# Atomic_V1_0_LDO.net
KiCad netlist of a schematic drawn in EAGLE
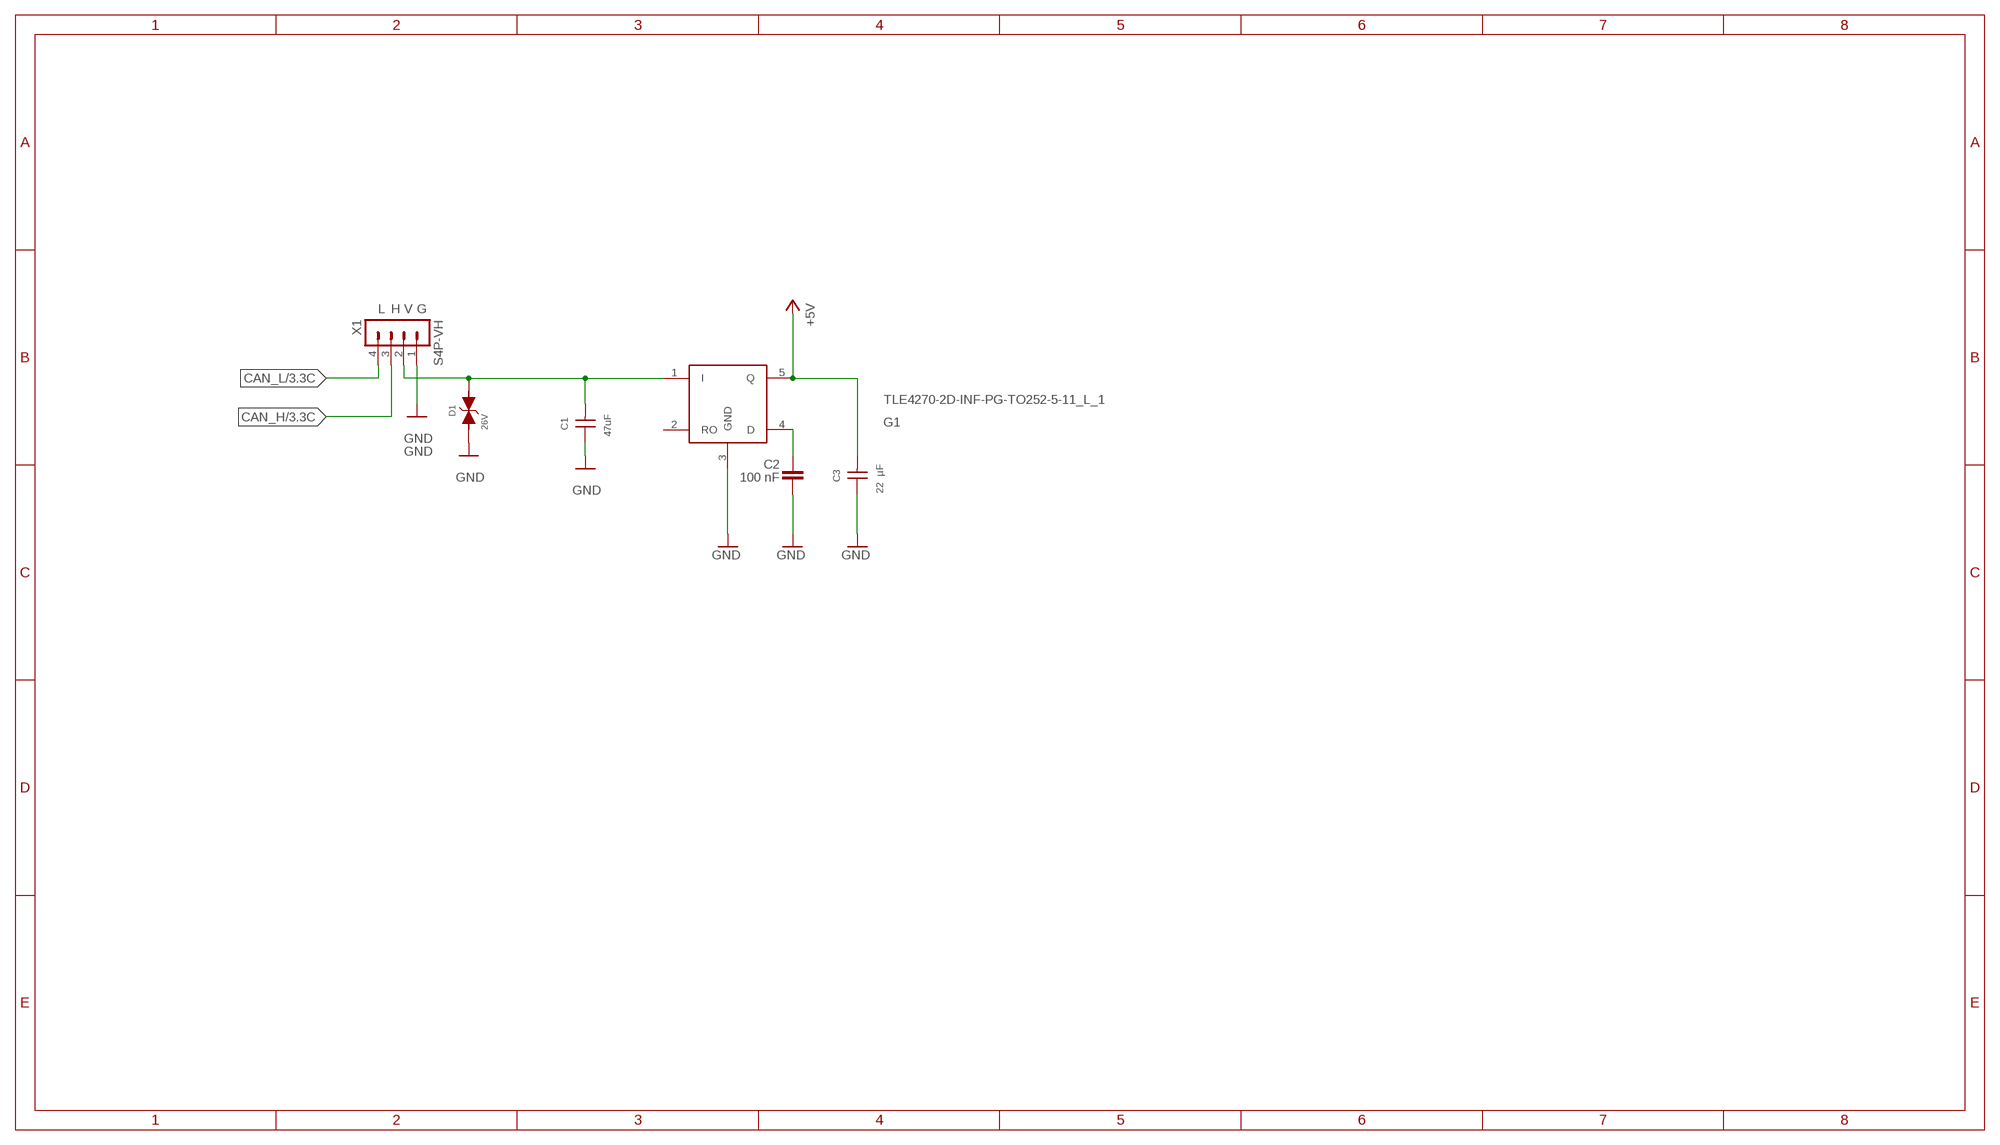
[diagram p0: schematic, sheet 1]
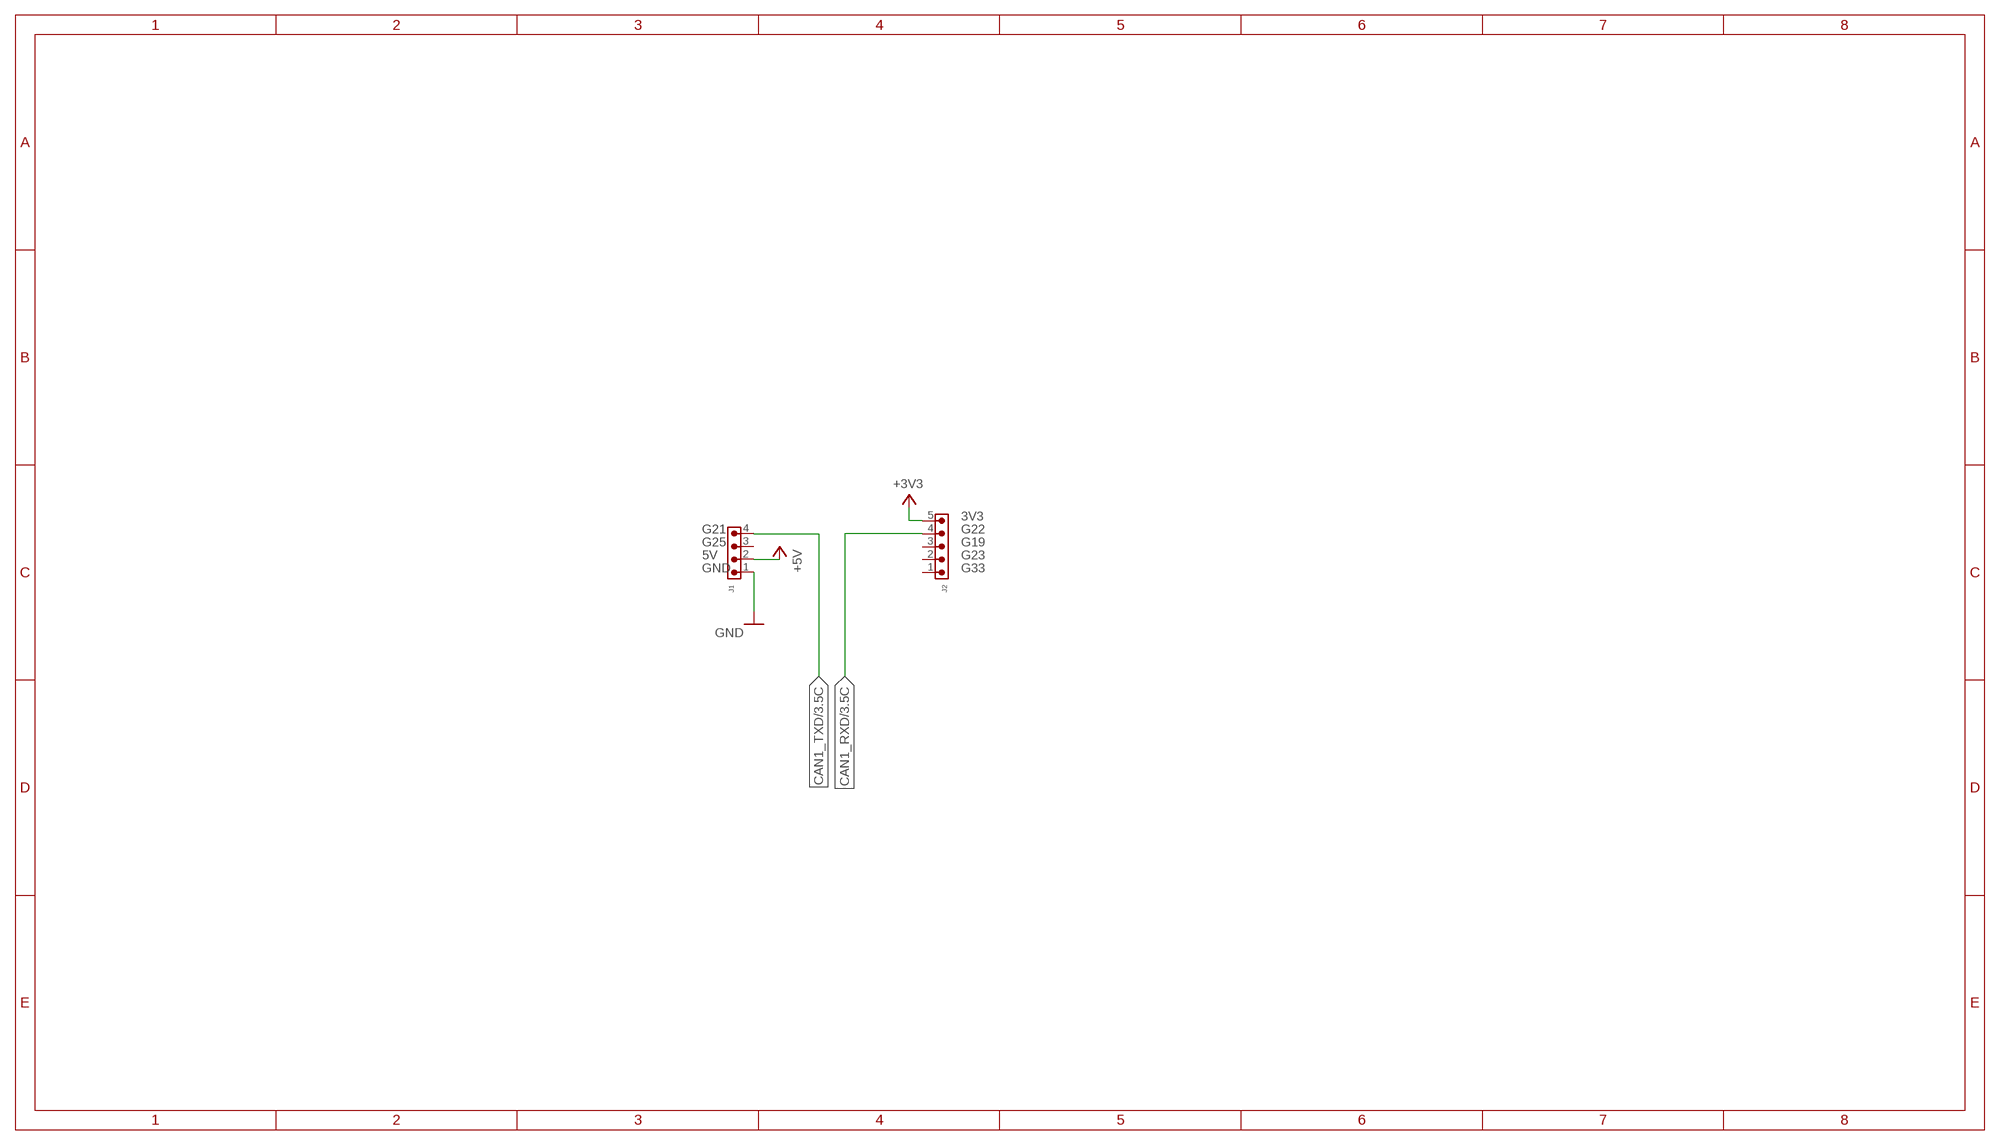
[diagram p1: schematic, sheet 2]
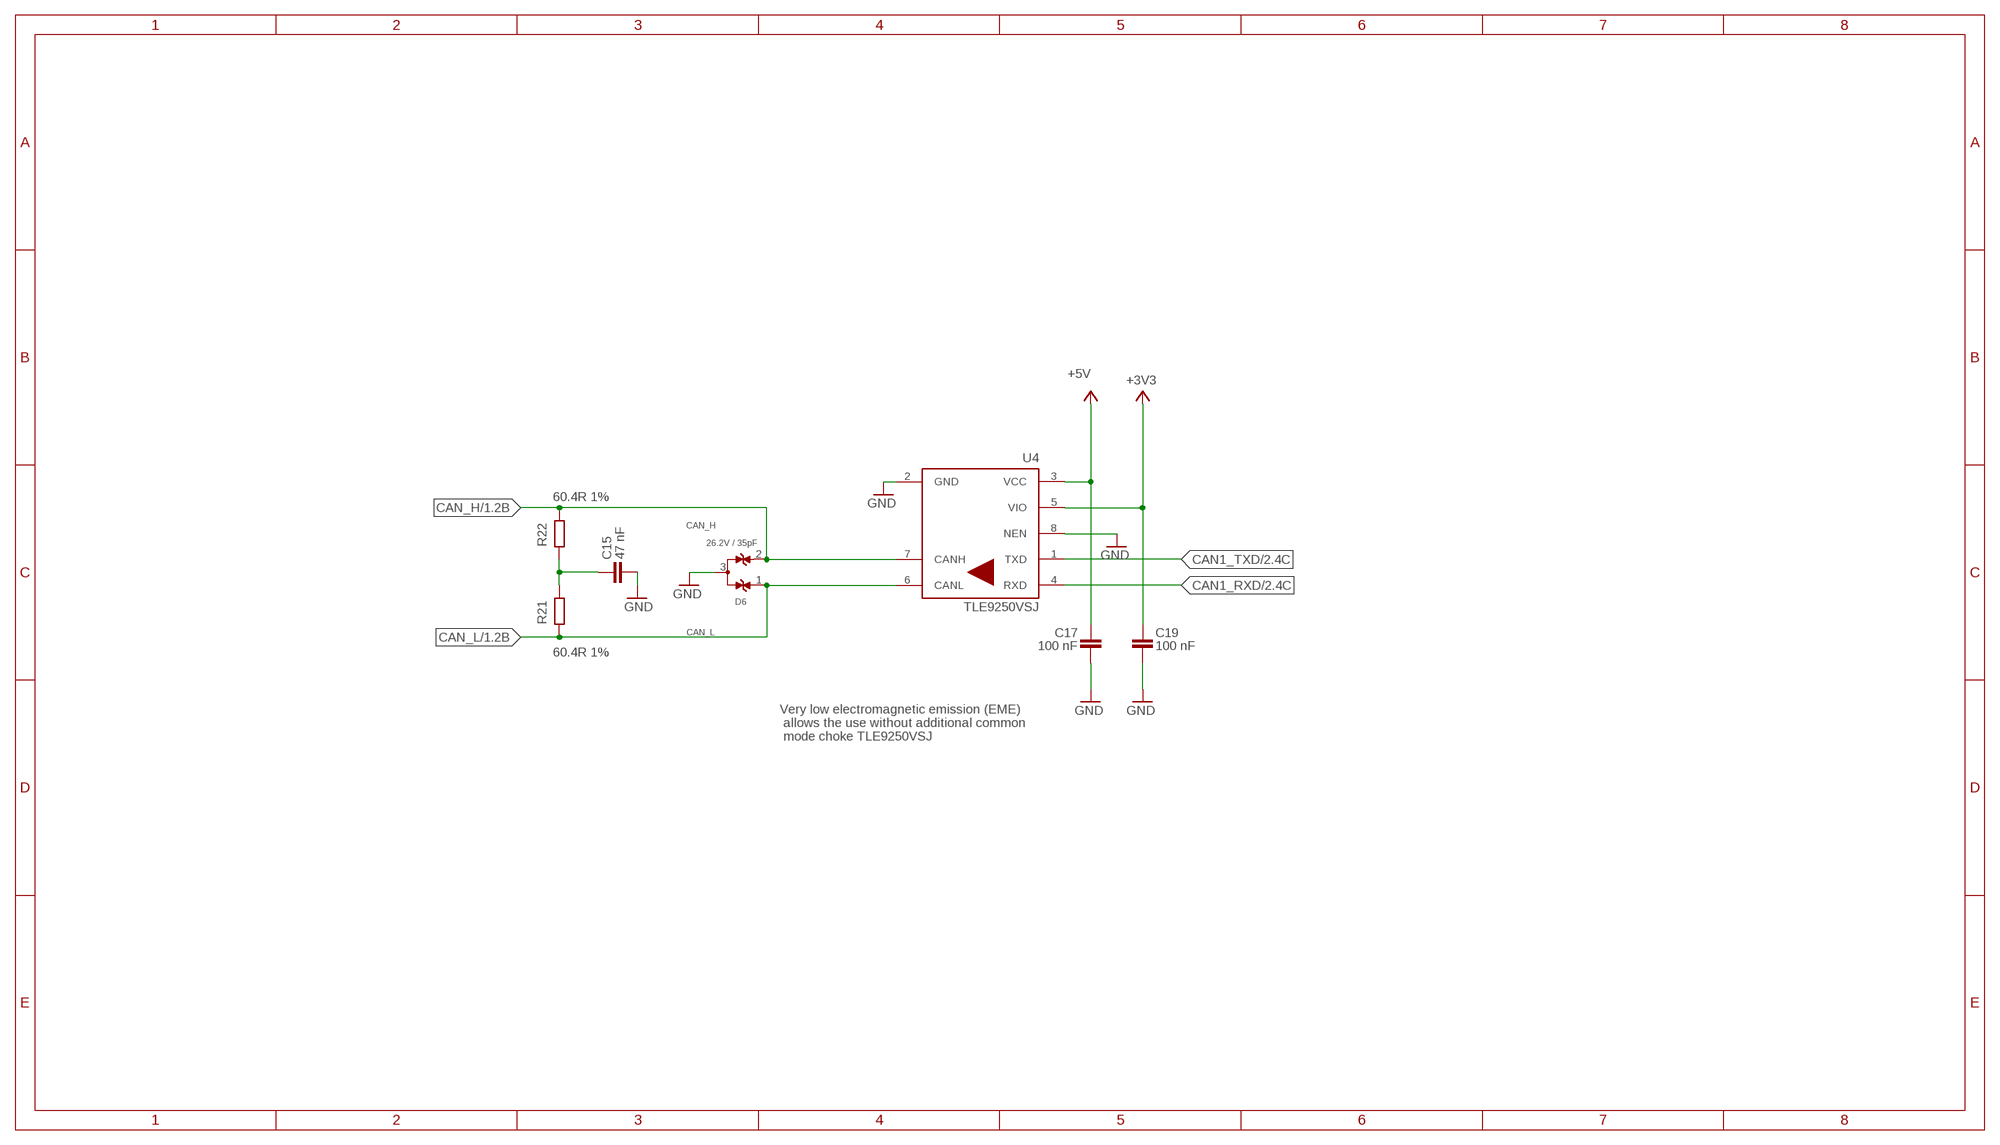
[diagram p2: schematic, sheet 3]

(export (version "E")
  (design (tool "Eeschema 10.0.6"))
  (components
    (comp (ref "C1")
      (value "47uF")
      (footprint "eagle-import:WCAP-CSGP_1210_H2.5")
      (libsource (lib "eagle-import") (part "WCAP-CSGP_1210_H2.5_25V(DC)_885012109014"))
    )
    (comp (ref "C2")
      (value "100 nF")
      (footprint "eagle-import:WCAP-CSGP_0402")
      (libsource (lib "eagle-import") (part "WCAP-CSGP_0402_16V(DC)_885012205037"))
    )
    (comp (ref "C3")
      (value "22 µF")
      (footprint "eagle-import:WCAP-CSGP_0805_H1.25_R")
      (libsource (lib "eagle-import") (part "WCAP-CSGP_0805_H1.25_10V(DC)_885012107011"))
    )
    (comp (ref "D1")
      (value "26V")
      (footprint "eagle-import:WE-TVSP_DO-214AC_BIDIRECTIONAL")
      (libsource (lib "eagle-import") (part "WE-TVSP_DO-214AC_400W_BI_824501261"))
    )
    (comp (ref "G1")
      (value "TLE4270-2D-INF-PG-TO252-5-11_L_1")
      (footprint "eagle-import:INF-PG-TO252-5-11_L_1PRIMARY")
      (libsource (lib "eagle-import") (part "TLE4270-2D-INF-PG-TO252-5-11_L_1"))
    )
    (comp (ref "X1")
      (value "S4P-VH")
      (footprint "eagle-import:S4P-VH")
      (libsource (lib "eagle-import") (part "S4P-VH"))
    )
    (comp (ref "J1")
      (value "6130XX11121_61300411121")
      (footprint "eagle-import:61300411121")
      (libsource (lib "eagle-import") (part "6130XX11121_61300411121"))
    )
    (comp (ref "J2")
      (value "6130XX11121_61300511121")
      (footprint "eagle-import:61300511121")
      (libsource (lib "eagle-import") (part "6130XX11121_61300511121"))
    )
    (comp (ref "C15")
      (value "47 nF")
      (footprint "eagle-import:WCAP-CSGP_0402")
      (libsource (lib "eagle-import") (part "WCAP-CSGP_0402_25V(DC)_885012205054"))
    )
    (comp (ref "C17")
      (value "100 nF")
      (footprint "eagle-import:WCAP-CSGP_0402")
      (libsource (lib "eagle-import") (part "WCAP-CSGP_0402_16V(DC)_885012205037"))
    )
    (comp (ref "C19")
      (value "100 nF")
      (footprint "eagle-import:WCAP-CSGP_0402")
      (libsource (lib "eagle-import") (part "WCAP-CSGP_0402_16V(DC)_885012205037"))
    )
    (comp (ref "D6")
      (value "26.2V / 35pF")
      (footprint "eagle-import:WE-TVS_SOT23-3L")
      (libsource (lib "eagle-import") (part "WE-TVS_SOT23-3L_824098024"))
    )
    (comp (ref "R21")
      (value "60.4R 1%")
      (footprint "eagle-import:WCAP-CSRF_0402")
      (fields (field (name "N") "SMD 0402 60.4ohms 1% AEC-Q200"))
      (libsource (lib "eagle-import") (part "R-0402_60.4OHMS_1%_AEC-Q200"))
    )
    (comp (ref "R22")
      (value "60.4R 1%")
      (footprint "eagle-import:WCAP-CSRF_0402")
      (fields (field (name "N") "SMD 0402 60.4ohms 1% AEC-Q200"))
      (libsource (lib "eagle-import") (part "R-0402_60.4OHMS_1%_AEC-Q200"))
    )
    (comp (ref "U4")
      (value "TLE9250VSJ")
      (footprint "eagle-import:SOIC127P602X173-8N-V")
      (libsource (lib "eagle-import") (part "TLE9250VSJ"))
    )
  )
  (nets
    (net (code "1") (name "+3V3") (class "Default")
      (node (ref "C19") (pin "1") (pinfunction "1_1") (pintype "passive"))
      (node (ref "J2") (pin "5") (pinfunction "5_5") (pintype "passive"))
      (node (ref "U4") (pin "5") (pinfunction "VIO_5") (pintype "input"))
    )
    (net (code "2") (name "+5V") (class "Default")
      (node (ref "C17") (pin "1") (pinfunction "1_1") (pintype "passive"))
      (node (ref "C3") (pin "2") (pinfunction "2_2") (pintype "passive"))
      (node (ref "G1") (pin "5") (pinfunction "Q_5") (pintype "power_in"))
      (node (ref "J1") (pin "2") (pinfunction "2_2") (pintype "passive"))
      (node (ref "U4") (pin "3") (pinfunction "VCC_3") (pintype "input"))
    )
    (net (code "3") (name "CAN1_RXD") (class "Default")
      (node (ref "J2") (pin "4") (pinfunction "4_4") (pintype "passive"))
      (node (ref "U4") (pin "4") (pinfunction "RXD_4") (pintype "output"))
    )
    (net (code "4") (name "CAN1_TXD") (class "Default")
      (node (ref "J1") (pin "4") (pinfunction "4_4") (pintype "passive"))
      (node (ref "U4") (pin "1") (pinfunction "TXD_1") (pintype "input"))
    )
    (net (code "5") (name "CAN_H") (class "Default")
      (node (ref "D6") (pin "2") (pinfunction "2_2") (pintype "passive"))
      (node (ref "R22") (pin "2") (pinfunction "2_2") (pintype "passive"))
      (node (ref "U4") (pin "7") (pinfunction "CANH_7") (pintype "bidirectional"))
      (node (ref "X1") (pin "3") (pinfunction "3_3") (pintype "passive"))
    )
    (net (code "6") (name "CAN_L") (class "Default")
      (node (ref "D6") (pin "1") (pinfunction "1_1") (pintype "passive"))
      (node (ref "R21") (pin "1") (pinfunction "1_1") (pintype "passive"))
      (node (ref "U4") (pin "6") (pinfunction "CANL_6") (pintype "bidirectional"))
      (node (ref "X1") (pin "4") (pinfunction "4_4") (pintype "passive"))
    )
    (net (code "7") (name "GND") (class "Default")
      (node (ref "C1") (pin "1") (pinfunction "1_1") (pintype "passive"))
      (node (ref "C15") (pin "2") (pinfunction "2_2") (pintype "passive"))
      (node (ref "C17") (pin "2") (pinfunction "2_2") (pintype "passive"))
      (node (ref "C19") (pin "2") (pinfunction "2_2") (pintype "passive"))
      (node (ref "C2") (pin "2") (pinfunction "2_2") (pintype "passive"))
      (node (ref "C3") (pin "1") (pinfunction "1_1") (pintype "passive"))
      (node (ref "D1") (pin "1") (pinfunction "1_1") (pintype "passive"))
      (node (ref "D6") (pin "3") (pinfunction "3_3") (pintype "passive"))
      (node (ref "G1") (pin "3") (pinfunction "GND_3") (pintype "power_in"))
      (node (ref "J1") (pin "1") (pinfunction "1_1") (pintype "passive"))
      (node (ref "U4") (pin "2") (pinfunction "GND_2") (pintype "power_in"))
      (node (ref "U4") (pin "8") (pinfunction "NEN_8") (pintype "input"))
      (node (ref "X1") (pin "1") (pinfunction "1_1") (pintype "passive"))
    )
    (net (code "8") (name "Net-(C15-Pad1)") (class "Default")
      (node (ref "C15") (pin "1") (pinfunction "1_1") (pintype "passive"))
      (node (ref "R21") (pin "2") (pinfunction "2_2") (pintype "passive"))
      (node (ref "R22") (pin "1") (pinfunction "1_1") (pintype "passive"))
    )
    (net (code "9") (name "Net-(G1-D)") (class "Default")
      (node (ref "C2") (pin "1") (pinfunction "1_1") (pintype "passive"))
      (node (ref "G1") (pin "4") (pinfunction "D_4") (pintype "bidirectional"))
    )
    (net (code "10") (name "Net-(G1-I)") (class "Default")
      (node (ref "C1") (pin "2") (pinfunction "2_2") (pintype "passive"))
      (node (ref "D1") (pin "2") (pinfunction "2_2") (pintype "passive"))
      (node (ref "G1") (pin "1") (pinfunction "I_1") (pintype "power_in"))
      (node (ref "X1") (pin "2") (pinfunction "2_2") (pintype "passive"))
    )
    (net (code "11") (name "unconnected-(G1-RO-Pad2)") (class "Default")
      (node (ref "G1") (pin "2") (pinfunction "RO_2") (pintype "output"))
    )
    (net (code "12") (name "unconnected-(J1-Pad3)") (class "Default")
      (node (ref "J1") (pin "3") (pinfunction "3_3") (pintype "passive"))
    )
    (net (code "13") (name "unconnected-(J2-Pad1)") (class "Default")
      (node (ref "J2") (pin "1") (pinfunction "1_1") (pintype "passive"))
    )
    (net (code "14") (name "unconnected-(J2-Pad2)") (class "Default")
      (node (ref "J2") (pin "2") (pinfunction "2_2") (pintype "passive"))
    )
    (net (code "15") (name "unconnected-(J2-Pad3)") (class "Default")
      (node (ref "J2") (pin "3") (pinfunction "3_3") (pintype "passive"))
    )
  )
)
